# 180V_PWM_motor.net
KiCad netlist of a schematic drawn in EAGLE
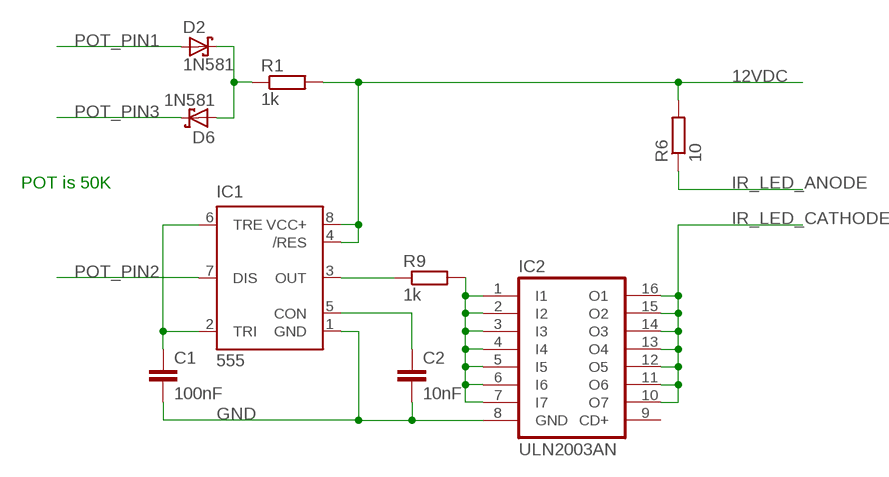
[diagram p0: schematic, sheet 1]
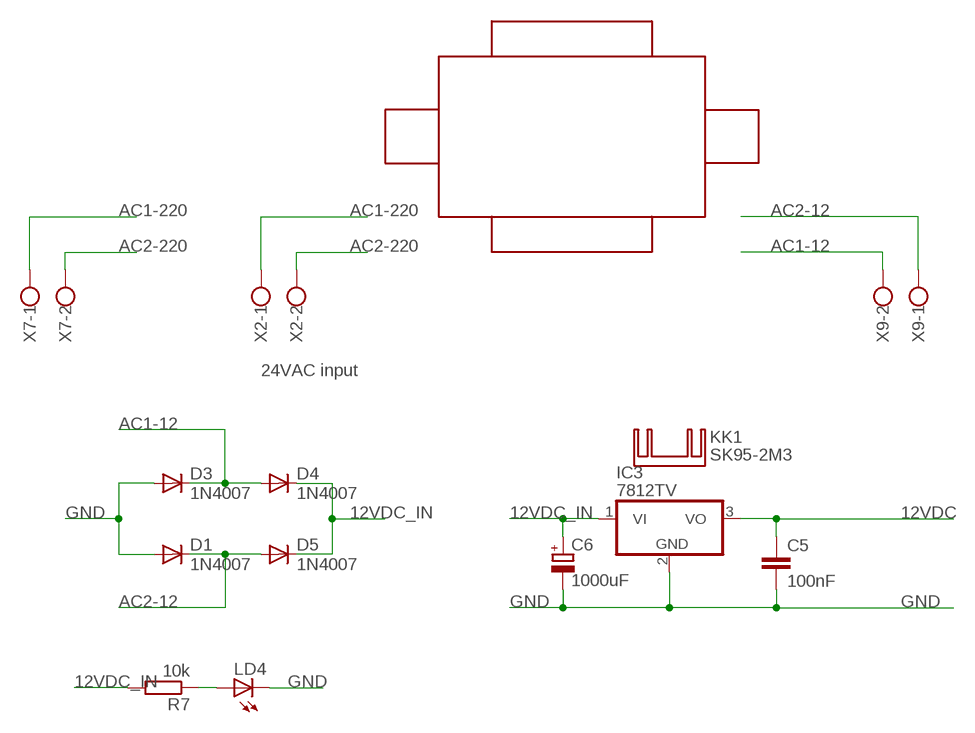
[diagram p1: schematic, sheet 2]

(export (version "E")
  (design (tool "Eeschema 10.0.6"))
  (components
    (comp (ref "C1")
      (value "100nF")
      (footprint "eagle-import:C050-025X075")
      (libsource (lib "eagle-import") (part "C-EU050-025X075"))
    )
    (comp (ref "C2")
      (value "10nF")
      (footprint "eagle-import:C050-025X075")
      (libsource (lib "eagle-import") (part "C-EU050-025X075"))
    )
    (comp (ref "D2")
      (value "1N581")
      (footprint "eagle-import:DO41-7.6")
      (libsource (lib "eagle-import") (part "1N5819-B"))
    )
    (comp (ref "D6")
      (value "1N581")
      (footprint "eagle-import:DO41-7.6")
      (libsource (lib "eagle-import") (part "1N5819-B"))
    )
    (comp (ref "IC1")
      (value "555")
      (footprint "eagle-import:DIP08")
      (libsource (lib "eagle-import") (part "555P"))
    )
    (comp (ref "IC2")
      (value "ULN2003AN")
      (footprint "eagle-import:DIL16")
      (libsource (lib "eagle-import") (part "ULN2003AN"))
    )
    (comp (ref "R1")
      (value "1k")
      (footprint "eagle-import:0207_10")
      (libsource (lib "eagle-import") (part "R-EU_0207/10"))
    )
    (comp (ref "R6")
      (value "10")
      (footprint "eagle-import:0207_10")
      (libsource (lib "eagle-import") (part "R-EU_0207/10"))
    )
    (comp (ref "R9")
      (value "1k")
      (footprint "eagle-import:0207_10")
      (libsource (lib "eagle-import") (part "R-EU_0207/10"))
    )
    (comp (ref "C5")
      (value "100nF")
      (footprint "eagle-import:C050-025X075")
      (libsource (lib "eagle-import") (part "C-EU050-025X075"))
    )
    (comp (ref "C6")
      (value "1000uF")
      (footprint "eagle-import:E3,5-10")
      (libsource (lib "eagle-import") (part "CPOL-EUE3.5-10"))
    )
    (comp (ref "D1")
      (value "1N4007")
      (footprint "eagle-import:DO41-10")
      (libsource (lib "eagle-import") (part "1N4004"))
    )
    (comp (ref "D3")
      (value "1N4007")
      (footprint "eagle-import:DO41-10")
      (libsource (lib "eagle-import") (part "1N4004"))
    )
    (comp (ref "D4")
      (value "1N4007")
      (footprint "eagle-import:DO41-10")
      (libsource (lib "eagle-import") (part "1N4004"))
    )
    (comp (ref "D5")
      (value "1N4007")
      (footprint "eagle-import:DO41-10")
      (libsource (lib "eagle-import") (part "1N4004"))
    )
    (comp (ref "IC3")
      (value "7812TV")
      (footprint "eagle-import:TO220V")
      (libsource (lib "eagle-import") (part "78TV12"))
    )
    (comp (ref "KK1")
      (value "SK95-2M3")
      (footprint "eagle-import:SK95-2M3")
      (libsource (lib "eagle-import") (part "SK95-2M3"))
    )
    (comp (ref "LD4")
      (value "LED5MM")
      (footprint "eagle-import:LED5MM")
      (libsource (lib "eagle-import") (part "LED5MM"))
    )
    (comp (ref "R7")
      (value "10k")
      (footprint "eagle-import:0207_10")
      (libsource (lib "eagle-import") (part "rcl-2_R-EU_0207/10"))
    )
    (comp (ref "U$1")
      (value "TRANS_12V")
      (footprint "eagle-import:12V")
      (libsource (lib "eagle-import") (part "TRANS_12V"))
    )
    (comp (ref "X2")
      (value "W237-102")
      (footprint "eagle-import:W237-102")
      (libsource (lib "eagle-import") (part "W237-102"))
    )
    (comp (ref "X7")
      (value "W237-102")
      (footprint "eagle-import:W237-102")
      (libsource (lib "eagle-import") (part "W237-102"))
    )
    (comp (ref "X9")
      (value "W237-102")
      (footprint "eagle-import:W237-102")
      (libsource (lib "eagle-import") (part "W237-102"))
    )
  )
  (nets
    (net (code "1") (name "12VDC") (class "Default")
      (node (ref "C5") (pin "1") (pinfunction "1_1") (pintype "passive"))
      (node (ref "IC1") (pin "4") (pinfunction "/RES_4") (pintype "input"))
      (node (ref "IC1") (pin "8") (pinfunction "VCC+_8") (pintype "power_in"))
      (node (ref "IC3") (pin "3") (pinfunction "VO_3") (pintype "passive"))
      (node (ref "R1") (pin "2") (pinfunction "2_2") (pintype "passive"))
      (node (ref "R6") (pin "2") (pinfunction "2_2") (pintype "passive"))
    )
    (net (code "2") (name "12VDC_IN") (class "Default")
      (node (ref "C6") (pin "+") (pinfunction "+_+") (pintype "passive"))
      (node (ref "D4") (pin "C") (pinfunction "C_C") (pintype "passive"))
      (node (ref "D5") (pin "C") (pinfunction "C_C") (pintype "passive"))
      (node (ref "IC3") (pin "1") (pinfunction "VI_1") (pintype "input"))
      (node (ref "R7") (pin "2") (pinfunction "2_2") (pintype "passive"))
    )
    (net (code "3") (name "AC1-12") (class "Default")
      (node (ref "D3") (pin "C") (pinfunction "C_C") (pintype "passive"))
      (node (ref "D4") (pin "A") (pinfunction "A_A") (pintype "passive"))
      (node (ref "X9") (pin "2") (pinfunction "KL_2") (pintype "passive"))
    )
    (net (code "4") (name "AC1-220") (class "Default")
      (node (ref "X2") (pin "1") (pinfunction "KL_1") (pintype "passive"))
      (node (ref "X7") (pin "1") (pinfunction "KL_1") (pintype "passive"))
    )
    (net (code "5") (name "AC2-12") (class "Default")
      (node (ref "D1") (pin "C") (pinfunction "C_C") (pintype "passive"))
      (node (ref "D5") (pin "A") (pinfunction "A_A") (pintype "passive"))
      (node (ref "X9") (pin "1") (pinfunction "KL_1") (pintype "passive"))
    )
    (net (code "6") (name "AC2-220") (class "Default")
      (node (ref "X2") (pin "2") (pinfunction "KL_2") (pintype "passive"))
      (node (ref "X7") (pin "2") (pinfunction "KL_2") (pintype "passive"))
    )
    (net (code "7") (name "GND") (class "Default")
      (node (ref "C1") (pin "2") (pinfunction "2_2") (pintype "passive"))
      (node (ref "C2") (pin "2") (pinfunction "2_2") (pintype "passive"))
      (node (ref "C5") (pin "2") (pinfunction "2_2") (pintype "passive"))
      (node (ref "C6") (pin "-") (pinfunction "-_-") (pintype "passive"))
      (node (ref "D1") (pin "A") (pinfunction "A_A") (pintype "passive"))
      (node (ref "D3") (pin "A") (pinfunction "A_A") (pintype "passive"))
      (node (ref "IC1") (pin "1") (pinfunction "GND_1") (pintype "power_in"))
      (node (ref "IC2") (pin "8") (pinfunction "GND_8") (pintype "power_in"))
      (node (ref "IC3") (pin "2") (pinfunction "GND_2") (pintype "passive"))
      (node (ref "LD4") (pin "K") (pinfunction "C_K") (pintype "passive"))
    )
    (net (code "8") (name "IR_LED_ANODE") (class "Default")
      (node (ref "R6") (pin "1") (pinfunction "1_1") (pintype "passive"))
    )
    (net (code "9") (name "IR_LED_CATHODE") (class "Default")
      (node (ref "IC2") (pin "10") (pinfunction "O7_10") (pintype "open_collector"))
      (node (ref "IC2") (pin "11") (pinfunction "O6_11") (pintype "open_collector"))
      (node (ref "IC2") (pin "12") (pinfunction "O5_12") (pintype "open_collector"))
      (node (ref "IC2") (pin "13") (pinfunction "O4_13") (pintype "open_collector"))
      (node (ref "IC2") (pin "14") (pinfunction "O3_14") (pintype "open_collector"))
      (node (ref "IC2") (pin "15") (pinfunction "O2_15") (pintype "open_collector"))
      (node (ref "IC2") (pin "16") (pinfunction "O1_16") (pintype "open_collector"))
    )
    (net (code "10") (name "Net-(D2-PadC)") (class "Default")
      (node (ref "D2") (pin "C") (pinfunction "C_C") (pintype "passive"))
      (node (ref "D6") (pin "A") (pinfunction "A_A") (pintype "passive"))
      (node (ref "R1") (pin "1") (pinfunction "1_1") (pintype "passive"))
    )
    (net (code "11") (name "Net-(IC1-CON)") (class "Default")
      (node (ref "C2") (pin "1") (pinfunction "1_1") (pintype "passive"))
      (node (ref "IC1") (pin "5") (pinfunction "CON_5") (pintype "input"))
    )
    (net (code "12") (name "Net-(IC1-OUT)") (class "Default")
      (node (ref "IC1") (pin "3") (pinfunction "OUT_3") (pintype "output"))
      (node (ref "R9") (pin "1") (pinfunction "1_1") (pintype "passive"))
    )
    (net (code "13") (name "Net-(IC1-TRE)") (class "Default")
      (node (ref "C1") (pin "1") (pinfunction "1_1") (pintype "passive"))
      (node (ref "IC1") (pin "2") (pinfunction "TRI_2") (pintype "input"))
      (node (ref "IC1") (pin "6") (pinfunction "TRE_6") (pintype "input"))
    )
    (net (code "14") (name "Net-(IC2-I1)") (class "Default")
      (node (ref "IC2") (pin "1") (pinfunction "I1_1") (pintype "input"))
      (node (ref "IC2") (pin "2") (pinfunction "I2_2") (pintype "input"))
      (node (ref "IC2") (pin "3") (pinfunction "I3_3") (pintype "input"))
      (node (ref "IC2") (pin "4") (pinfunction "I4_4") (pintype "input"))
      (node (ref "IC2") (pin "5") (pinfunction "I5_5") (pintype "input"))
      (node (ref "IC2") (pin "6") (pinfunction "I6_6") (pintype "input"))
      (node (ref "IC2") (pin "7") (pinfunction "I7_7") (pintype "input"))
      (node (ref "R9") (pin "2") (pinfunction "2_2") (pintype "passive"))
    )
    (net (code "15") (name "Net-(LD4-PadA)") (class "Default")
      (node (ref "LD4") (pin "A") (pinfunction "A_A") (pintype "passive"))
      (node (ref "R7") (pin "1") (pinfunction "1_1") (pintype "passive"))
    )
    (net (code "16") (name "POT_PIN1") (class "Default")
      (node (ref "D2") (pin "A") (pinfunction "A_A") (pintype "passive"))
    )
    (net (code "17") (name "POT_PIN2") (class "Default")
      (node (ref "IC1") (pin "7") (pinfunction "DIS_7") (pintype "input"))
    )
    (net (code "18") (name "POT_PIN3") (class "Default")
      (node (ref "D6") (pin "C") (pinfunction "C_C") (pintype "passive"))
    )
    (net (code "19") (name "unconnected-(IC2-CD+-Pad9)") (class "Default")
      (node (ref "IC2") (pin "9") (pinfunction "CD+_9") (pintype "passive"))
    )
  )
)
